# P02_MPU1_JTAG.net
KiCad netlist of a schematic drawn in Altium Designer
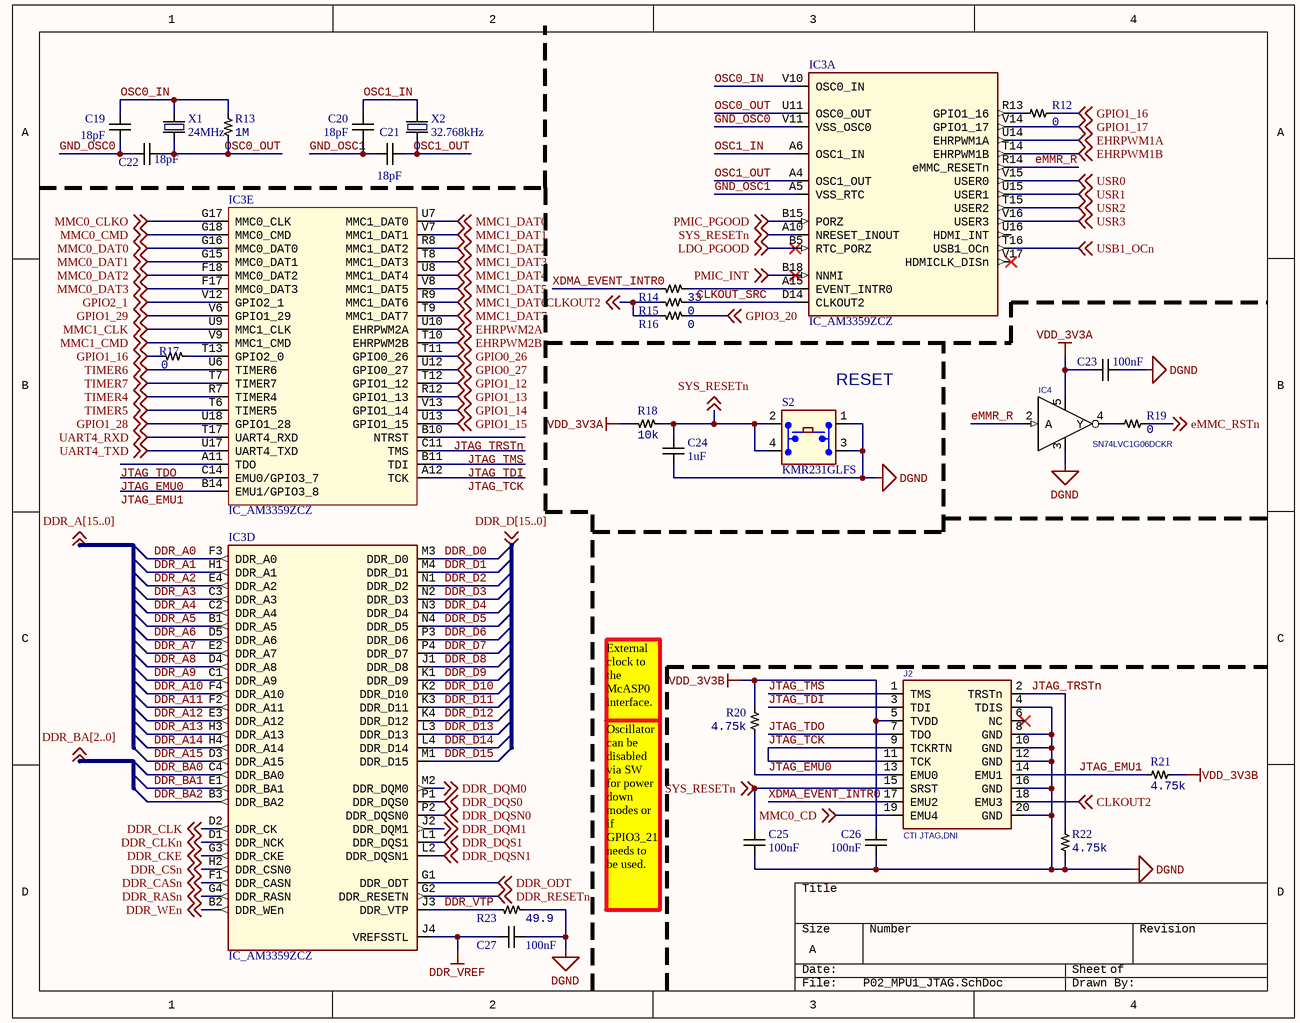
[diagram p0: P02_MPU1_JTAG.SchDoc]

(export (version "E")
  (design (tool "Eeschema 10.0.6"))
  (components
    (comp (ref "C19")
      (value "CC0402JRNPO9BN180")
      (footprint "Orient:CAP0402")
      (description "MLCC 18pF 0402 SMD")
      (fields
        (field (name "MANUFACTURER") "Yageo")
        (field (name "CAPACITANCE") "18pF")
        (field (name "TOLERANCE") "5%")
      )
      (libsource (lib "Orient") (part "CAP_18pF"))
    )
    (comp (ref "C20")
      (value "CC0402JRNPO9BN180")
      (footprint "Orient:CAP0402")
      (description "MLCC 18pF 0402 SMD")
      (fields
        (field (name "MANUFACTURER") "Yageo")
        (field (name "CAPACITANCE") "18pF")
        (field (name "TOLERANCE") "5%")
      )
      (libsource (lib "Orient") (part "CAP_18pF"))
    )
    (comp (ref "C21")
      (value "CC0402JRNPO9BN180")
      (footprint "Orient:CAP0402")
      (description "MLCC 18pF 0402 SMD")
      (fields
        (field (name "MANUFACTURER") "Yageo")
        (field (name "CAPACITANCE") "18pF")
        (field (name "TOLERANCE") "5%")
      )
      (libsource (lib "Orient") (part "CAP_18pF"))
    )
    (comp (ref "C22")
      (value "CC0402JRNPO9BN180")
      (footprint "Orient:CAP0402")
      (description "MLCC 18pF 0402 SMD")
      (fields
        (field (name "MANUFACTURER") "Yageo")
        (field (name "CAPACITANCE") "18pF")
        (field (name "TOLERANCE") "5%")
      )
      (libsource (lib "Orient") (part "CAP_18pF"))
    )
    (comp (ref "C23")
      (value "C0402C104K4RACTU")
      (footprint "Orient:CAP0402")
      (description "MLCC 100nF 0402 SMD")
      (fields
        (field (name "MANUFACTURER") "KEMET")
        (field (name "TOLERANCE") "10%")
        (field (name "CAPACITANCE") "100nF")
      )
      (libsource (lib "Orient") (part "CAP_100nF"))
    )
    (comp (ref "C24")
      (value "CC0402KRX5R6BB105")
      (footprint "Orient:CAP0402")
      (description "MLCC 1uF 0402 SMD")
      (fields
        (field (name "CAPACITANCE") "1uF")
        (field (name "MANUFACTURER") "Yageo")
        (field (name "TOLERANCE") "10%")
      )
      (libsource (lib "Orient") (part "CAP_1uF"))
    )
    (comp (ref "C25")
      (value "C0402C104K4RACTU")
      (footprint "Orient:CAP0402")
      (description "MLCC 100nF 0402 SMD")
      (fields
        (field (name "MANUFACTURER") "KEMET")
        (field (name "TOLERANCE") "10%")
        (field (name "CAPACITANCE") "100nF")
      )
      (libsource (lib "Orient") (part "CAP_100nF"))
    )
    (comp (ref "C26")
      (value "C0402C104K4RACTU")
      (footprint "Orient:CAP0402")
      (description "MLCC 100nF 0402 SMD")
      (fields
        (field (name "MANUFACTURER") "KEMET")
        (field (name "TOLERANCE") "10%")
        (field (name "CAPACITANCE") "100nF")
      )
      (libsource (lib "Orient") (part "CAP_100nF"))
    )
    (comp (ref "C27")
      (value "C0402C104K4RACTU")
      (footprint "Orient:CAP0402")
      (description "MLCC 100nF 0402 SMD")
      (fields
        (field (name "MANUFACTURER") "KEMET")
        (field (name "TOLERANCE") "10%")
        (field (name "CAPACITANCE") "100nF")
      )
      (libsource (lib "Orient") (part "CAP_100nF"))
    )
    (comp (ref "IC3")
      (value "IC_AM3359ZCZ")
      (footprint "Orient:BGA-324")
      (description "SubArctic Cortex A8 Processor 18x18")
      (fields
        (field (name "MANUFACTURER") "Texas Instruments")
        (field (name "MANUFACTURER PART NUMBER") "XAM3359ZCZ")
      )
      (libsource (lib "Orient") (part "IC_AM335X_ZCE_1"))
    )
    (comp (ref "IC4")
      (value "SN74LVC1G06DCKR")
      (footprint "Orient:SC70_DCK")
      (description "IC INVERTER SINGLE 1INPUT SC705")
      (fields
        (field (name "MANUFACTURER") "Texas Instruments")
        (field (name "MANUFACTURER PART NUMBER") "SN74LVC1G06DCKTG4")
      )
      (libsource (lib "Orient") (part "IC_Inverter"))
    )
    (comp (ref "J2")
      (value "CTI JTAG,DNI")
      (description "Dual Line Header 10x2pin Tin")
      (fields
        (field (name "MANUFACTURER") "Samtec Inc")
        (field (name "MANUFACTURER PART NUMBER") "FTR-110-03-G-D-06")
      )
      (libsource (lib "Orient") (part "HDR_10x2_CJTAG"))
    )
    (comp (ref "R12")
      (value "RC0402JR-070RL")
      (footprint "Orient:RES0402")
      (description "Resistor 0Ohm 0402 SMD")
      (fields
        (field (name "MANUFACTURER") "Yageo")
        (field (name "TOLERANCE") "5%")
        (field (name "RESISTANCE") "0")
      )
      (libsource (lib "Orient") (part "RES_0"))
    )
    (comp (ref "R13")
      (value "RC0402FR-071ML")
      (footprint "Orient:RES0402")
      (description "Resistor 1MOhm 0402 SMD")
      (fields
        (field (name "MANUFACTURER") "Yageo")
        (field (name "TOLERANCE") "1%")
        (field (name "RESISTANCE") "1M")
      )
      (libsource (lib "Orient") (part "RES_1M"))
    )
    (comp (ref "R14")
      (value "RC0402FR-0733RL")
      (footprint "Orient:RES0402")
      (description "Resistor 33Ohm 0402 SMD")
      (fields
        (field (name "MANUFACTURER") "Yageo")
        (field (name "TOLERANCE") "1%")
        (field (name "RESISTANCE") "33")
      )
      (libsource (lib "Orient") (part "RES_33"))
    )
    (comp (ref "R15")
      (value "RC0402JR-070RL")
      (footprint "Orient:RES0402")
      (description "Resistor 0Ohm 0402 SMD")
      (fields
        (field (name "MANUFACTURER") "Yageo")
        (field (name "TOLERANCE") "5%")
        (field (name "RESISTANCE") "0")
      )
      (libsource (lib "Orient") (part "RES_0"))
    )
    (comp (ref "R16")
      (value "RC0402JR-070RL")
      (footprint "Orient:RES0402")
      (description "Resistor 0Ohm 0402 SMD")
      (fields
        (field (name "MANUFACTURER") "Yageo")
        (field (name "TOLERANCE") "5%")
        (field (name "RESISTANCE") "0")
      )
      (libsource (lib "Orient") (part "RES_0"))
    )
    (comp (ref "R17")
      (value "RC0402JR-070RL")
      (footprint "Orient:RES0402")
      (description "Resistor 0Ohm 0402 SMD")
      (fields
        (field (name "MANUFACTURER") "Yageo")
        (field (name "TOLERANCE") "5%")
        (field (name "RESISTANCE") "0")
      )
      (libsource (lib "Orient") (part "RES_0"))
    )
    (comp (ref "R18")
      (value "RC0402FR-0710KL")
      (footprint "Orient:RES0402")
      (description "Resistor 10kOhm 0402 SMD")
      (fields
        (field (name "MANUFACTURER") "Yageo")
        (field (name "TOLERANCE") "1%")
        (field (name "RESISTANCE") "10k")
      )
      (libsource (lib "Orient") (part "RES_10k"))
    )
    (comp (ref "R19")
      (value "RC0402JR-070RL")
      (footprint "Orient:RES0402")
      (description "Resistor 0Ohm 0402 SMD")
      (fields
        (field (name "MANUFACTURER") "Yageo")
        (field (name "TOLERANCE") "5%")
        (field (name "RESISTANCE") "0")
      )
      (libsource (lib "Orient") (part "RES_0"))
    )
    (comp (ref "R20")
      (value "RC0402FR-074K75L")
      (footprint "Orient:RES0402")
      (description "Resistor 4.75kOhm 0402 SMD")
      (fields
        (field (name "MANUFACTURER") "Yageo")
        (field (name "TOLERANCE") "1%")
        (field (name "RESISTANCE") "4.75k")
      )
      (libsource (lib "Orient") (part "RES_4.75k"))
    )
    (comp (ref "R21")
      (value "RC0402FR-074K75L")
      (footprint "Orient:RES0402")
      (description "Resistor 4.75kOhm 0402 SMD")
      (fields
        (field (name "MANUFACTURER") "Yageo")
        (field (name "TOLERANCE") "1%")
        (field (name "RESISTANCE") "4.75k")
      )
      (libsource (lib "Orient") (part "RES_4.75k"))
    )
    (comp (ref "R22")
      (value "RC0402FR-074K75L")
      (footprint "Orient:RES0402")
      (description "Resistor 4.75kOhm 0402 SMD")
      (fields
        (field (name "MANUFACTURER") "Yageo")
        (field (name "TOLERANCE") "1%")
        (field (name "RESISTANCE") "4.75k")
      )
      (libsource (lib "Orient") (part "RES_4.75k"))
    )
    (comp (ref "R23")
      (value "RC0402FR-0749R9")
      (footprint "Orient:RES0402")
      (description "Resistor 49.9Ohm 0402 SMD")
      (fields
        (field (name "MANUFACTURER") "Yageo")
        (field (name "MANUFACTURER PART NUMBER") "RC0402FR-0749R9L")
        (field (name "RESISTANCE") "49.9")
      )
      (libsource (lib "Orient") (part "RES_49.9"))
    )
    (comp (ref "S2")
      (value "KMR231GLFS")
      (footprint "Orient:SW4SMD_63X161LS")
      (description "Microminiature Tact Switch for SMT")
      (fields (field (name "MANUFACTURER") "C&K Components"))
      (libsource (lib "Orient") (part "KMR2"))
    )
    (comp (ref "X1")
      (value "24MHz")
      (footprint "Orient:XTAL150SMD_125X196")
      (description "CRYSTAL 24.000MHZ 18PF SMD")
      (fields
        (field (name "MANUFACTURER") "TXC CORPORATION")
        (field (name "MANUFACTURER PART NUMBER") "7A-24.000MAAJ-T")
      )
      (libsource (lib "Orient") (part "CRYS_24MHz_SCC"))
    )
    (comp (ref "X2")
      (value "32.768kHz")
      (footprint "Orient:SOJ-4")
      (description "CRYSTAL 32.768KHZ 12.5PF SMD")
      (fields
        (field (name "MANUFACTURER") "Citizen Finetech Miyota")
        (field (name "MANUFACTURER PART NUMBER") "CM200C-32.768KAZF-UT")
      )
      (libsource (lib "Orient") (part "CRYS_32.768kHz"))
    )
  )
  (nets
    (net (code "1") (name "/CLKOUT_SRC") (class "Default")
      (node (ref "IC3") (pin "D14") (pinfunction "CLKOUT2_D14") (pintype "bidirectional"))
      (node (ref "R15") (pin "1") (pintype "passive"))
    )
    (net (code "2") (name "/DDR_VTP") (class "Default")
      (node (ref "IC3") (pin "J3") (pinfunction "DDR_VTP_J3") (pintype "passive"))
      (node (ref "R23") (pin "2") (pintype "passive"))
    )
    (net (code "3") (name "/GND_OSC0") (class "Default")
      (node (ref "C19") (pin "2") (pintype "passive"))
      (node (ref "C22") (pin "1") (pintype "passive"))
      (node (ref "IC3") (pin "V11") (pinfunction "VSS_OSC0_V11") (pintype "power_in"))
    )
    (net (code "4") (name "/GND_OSC1") (class "Default")
      (node (ref "C20") (pin "1") (pintype "passive"))
      (node (ref "C21") (pin "2") (pintype "passive"))
      (node (ref "IC3") (pin "A5") (pinfunction "VSS_RTC_A5") (pintype "power_in"))
    )
    (net (code "5") (name "/JTAG_EMU0") (class "Default")
      (node (ref "IC3") (pin "C14") (pinfunction "EMU0/GPIO3_7_C14") (pintype "passive"))
      (node (ref "J2") (pin "13") (pinfunction "EMU0_13") (pintype "passive"))
      (node (ref "R20") (pin "1") (pintype "passive"))
    )
    (net (code "6") (name "/JTAG_EMU1") (class "Default")
      (node (ref "IC3") (pin "B14") (pinfunction "EMU1/GPIO3_8_B14") (pintype "passive"))
      (node (ref "J2") (pin "14") (pinfunction "EMU1_14") (pintype "passive"))
      (node (ref "R21") (pin "2") (pintype "passive"))
    )
    (net (code "7") (name "/JTAG_TCK") (class "Default")
      (node (ref "IC3") (pin "A12") (pinfunction "TCK_A12") (pintype "passive"))
      (node (ref "J2") (pin "11") (pinfunction "TCK_11") (pintype "passive"))
      (node (ref "J2") (pin "9") (pinfunction "TCKRTN_9") (pintype "passive"))
    )
    (net (code "8") (name "/JTAG_TDI") (class "Default")
      (node (ref "IC3") (pin "B11") (pinfunction "TDI_B11") (pintype "passive"))
      (node (ref "J2") (pin "3") (pinfunction "TDI_3") (pintype "passive"))
    )
    (net (code "9") (name "/JTAG_TDO") (class "Default")
      (node (ref "IC3") (pin "A11") (pinfunction "TDO_A11") (pintype "passive"))
      (node (ref "J2") (pin "7") (pinfunction "TDO_7") (pintype "passive"))
    )
    (net (code "10") (name "/JTAG_TMS") (class "Default")
      (node (ref "IC3") (pin "C11") (pinfunction "TMS_C11") (pintype "passive"))
      (node (ref "J2") (pin "1") (pinfunction "TMS_1") (pintype "passive"))
    )
    (net (code "11") (name "/JTAG_TRSTn") (class "Default")
      (node (ref "IC3") (pin "B10") (pinfunction "NTRST_B10") (pintype "passive"))
      (node (ref "J2") (pin "2") (pinfunction "TRSTn_2") (pintype "passive"))
      (node (ref "R22") (pin "2") (pintype "passive"))
    )
    (net (code "12") (name "/OSC0_IN") (class "Default")
      (node (ref "C19") (pin "1") (pintype "passive"))
      (node (ref "IC3") (pin "V10") (pinfunction "OSC0_IN_V10") (pintype "passive"))
      (node (ref "R13") (pin "2") (pintype "passive"))
      (node (ref "X1") (pin "2") (pinfunction "2_2") (pintype "passive"))
    )
    (net (code "13") (name "/OSC0_OUT") (class "Default")
      (node (ref "C22") (pin "2") (pintype "passive"))
      (node (ref "IC3") (pin "U11") (pinfunction "OSC0_OUT_U11") (pintype "passive"))
      (node (ref "R13") (pin "1") (pintype "passive"))
      (node (ref "X1") (pin "1") (pinfunction "1_1") (pintype "passive"))
    )
    (net (code "14") (name "/OSC1_IN") (class "Default")
      (node (ref "C20") (pin "2") (pintype "passive"))
      (node (ref "IC3") (pin "A6") (pinfunction "OSC1_IN_A6") (pintype "passive"))
      (node (ref "X2") (pin "1") (pinfunction "1_1") (pintype "passive"))
    )
    (net (code "15") (name "/OSC1_OUT") (class "Default")
      (node (ref "C21") (pin "1") (pintype "passive"))
      (node (ref "IC3") (pin "A4") (pinfunction "OSC1_OUT_A4") (pintype "passive"))
      (node (ref "X2") (pin "4") (pinfunction "4_4") (pintype "passive"))
    )
    (net (code "16") (name "/XDMA_EVENT_INTR0") (class "Default")
      (node (ref "J2") (pin "17") (pinfunction "EMU2_17") (pintype "passive"))
      (node (ref "R14") (pin "1") (pintype "passive"))
    )
    (net (code "17") (name "/eMMR_R") (class "Default")
      (node (ref "IC3") (pin "R14") (pinfunction "eMMC_RESETn_R14") (pintype "output"))
      (node (ref "IC4") (pin "2") (pinfunction "A_2") (pintype "input"))
    )
    (net (code "18") (name "CLKOUT2") (class "Default")
      (node (ref "J2") (pin "18") (pinfunction "EMU3_18") (pintype "passive"))
      (node (ref "R15") (pin "2") (pintype "passive"))
      (node (ref "R16") (pin "2") (pintype "passive"))
    )
    (net (code "19") (name "DDR_A0") (class "Default")
      (node (ref "IC3") (pin "F3") (pinfunction "DDR_A0_F3") (pintype "output"))
    )
    (net (code "20") (name "DDR_A1") (class "Default")
      (node (ref "IC3") (pin "H1") (pinfunction "DDR_A1_H1") (pintype "output"))
    )
    (net (code "21") (name "DDR_A2") (class "Default")
      (node (ref "IC3") (pin "E4") (pinfunction "DDR_A2_E4") (pintype "output"))
    )
    (net (code "22") (name "DDR_A3") (class "Default")
      (node (ref "IC3") (pin "C3") (pinfunction "DDR_A3_C3") (pintype "output"))
    )
    (net (code "23") (name "DDR_A4") (class "Default")
      (node (ref "IC3") (pin "C2") (pinfunction "DDR_A4_C2") (pintype "output"))
    )
    (net (code "24") (name "DDR_A5") (class "Default")
      (node (ref "IC3") (pin "B1") (pinfunction "DDR_A5_B1") (pintype "output"))
    )
    (net (code "25") (name "DDR_A6") (class "Default")
      (node (ref "IC3") (pin "D5") (pinfunction "DDR_A6_D5") (pintype "output"))
    )
    (net (code "26") (name "DDR_A7") (class "Default")
      (node (ref "IC3") (pin "E2") (pinfunction "DDR_A7_E2") (pintype "output"))
    )
    (net (code "27") (name "DDR_A8") (class "Default")
      (node (ref "IC3") (pin "D4") (pinfunction "DDR_A8_D4") (pintype "output"))
    )
    (net (code "28") (name "DDR_A9") (class "Default")
      (node (ref "IC3") (pin "C1") (pinfunction "DDR_A9_C1") (pintype "output"))
    )
    (net (code "29") (name "DDR_A10") (class "Default")
      (node (ref "IC3") (pin "F4") (pinfunction "DDR_A10_F4") (pintype "output"))
    )
    (net (code "30") (name "DDR_A11") (class "Default")
      (node (ref "IC3") (pin "F2") (pinfunction "DDR_A11_F2") (pintype "output"))
    )
    (net (code "31") (name "DDR_A12") (class "Default")
      (node (ref "IC3") (pin "E3") (pinfunction "DDR_A12_E3") (pintype "output"))
    )
    (net (code "32") (name "DDR_A13") (class "Default")
      (node (ref "IC3") (pin "H3") (pinfunction "DDR_A13_H3") (pintype "output"))
    )
    (net (code "33") (name "DDR_A14") (class "Default")
      (node (ref "IC3") (pin "H4") (pinfunction "DDR_A14_H4") (pintype "output"))
    )
    (net (code "34") (name "DDR_A15") (class "Default")
      (node (ref "IC3") (pin "D3") (pinfunction "DDR_A15_D3") (pintype "output"))
    )
    (net (code "36") (name "DDR_BA0") (class "Default")
      (node (ref "IC3") (pin "C4") (pinfunction "DDR_BA0_C4") (pintype "output"))
    )
    (net (code "37") (name "DDR_BA1") (class "Default")
      (node (ref "IC3") (pin "E1") (pinfunction "DDR_BA1_E1") (pintype "output"))
    )
    (net (code "38") (name "DDR_BA2") (class "Default")
      (node (ref "IC3") (pin "B3") (pinfunction "DDR_BA2_B3") (pintype "output"))
    )
    (net (code "40") (name "DDR_CASn") (class "Default")
      (node (ref "IC3") (pin "F1") (pinfunction "DDR_CASN_F1") (pintype "output"))
    )
    (net (code "41") (name "DDR_CKE") (class "Default")
      (node (ref "IC3") (pin "G3") (pinfunction "DDR_CKE_G3") (pintype "output"))
    )
    (net (code "42") (name "DDR_CLK") (class "Default")
      (node (ref "IC3") (pin "D2") (pinfunction "DDR_CK_D2") (pintype "output"))
    )
    (net (code "43") (name "DDR_CLKn") (class "Default")
      (node (ref "IC3") (pin "D1") (pinfunction "DDR_NCK_D1") (pintype "output"))
    )
    (net (code "44") (name "DDR_CSn") (class "Default")
      (node (ref "IC3") (pin "H2") (pinfunction "DDR_CSN0_H2") (pintype "output"))
    )
    (net (code "45") (name "DDR_D0") (class "Default")
      (node (ref "IC3") (pin "M3") (pinfunction "DDR_D0_M3") (pintype "bidirectional"))
    )
    (net (code "46") (name "DDR_D1") (class "Default")
      (node (ref "IC3") (pin "M4") (pinfunction "DDR_D1_M4") (pintype "bidirectional"))
    )
    (net (code "47") (name "DDR_D2") (class "Default")
      (node (ref "IC3") (pin "N1") (pinfunction "DDR_D2_N1") (pintype "bidirectional"))
    )
    (net (code "48") (name "DDR_D3") (class "Default")
      (node (ref "IC3") (pin "N2") (pinfunction "DDR_D3_N2") (pintype "bidirectional"))
    )
    (net (code "49") (name "DDR_D4") (class "Default")
      (node (ref "IC3") (pin "N3") (pinfunction "DDR_D4_N3") (pintype "bidirectional"))
    )
    (net (code "50") (name "DDR_D5") (class "Default")
      (node (ref "IC3") (pin "N4") (pinfunction "DDR_D5_N4") (pintype "bidirectional"))
    )
    (net (code "51") (name "DDR_D6") (class "Default")
      (node (ref "IC3") (pin "P3") (pinfunction "DDR_D6_P3") (pintype "bidirectional"))
    )
    (net (code "52") (name "DDR_D7") (class "Default")
      (node (ref "IC3") (pin "P4") (pinfunction "DDR_D7_P4") (pintype "bidirectional"))
    )
    (net (code "53") (name "DDR_D8") (class "Default")
      (node (ref "IC3") (pin "J1") (pinfunction "DDR_D8_J1") (pintype "bidirectional"))
    )
    (net (code "54") (name "DDR_D9") (class "Default")
      (node (ref "IC3") (pin "K1") (pinfunction "DDR_D9_K1") (pintype "bidirectional"))
    )
    (net (code "55") (name "DDR_D10") (class "Default")
      (node (ref "IC3") (pin "K2") (pinfunction "DDR_D10_K2") (pintype "bidirectional"))
    )
    (net (code "56") (name "DDR_D11") (class "Default")
      (node (ref "IC3") (pin "K3") (pinfunction "DDR_D11_K3") (pintype "bidirectional"))
    )
    (net (code "57") (name "DDR_D12") (class "Default")
      (node (ref "IC3") (pin "K4") (pinfunction "DDR_D12_K4") (pintype "bidirectional"))
    )
    (net (code "58") (name "DDR_D13") (class "Default")
      (node (ref "IC3") (pin "L3") (pinfunction "DDR_D13_L3") (pintype "bidirectional"))
    )
    (net (code "59") (name "DDR_D14") (class "Default")
      (node (ref "IC3") (pin "L4") (pinfunction "DDR_D14_L4") (pintype "bidirectional"))
    )
    (net (code "60") (name "DDR_D15") (class "Default")
      (node (ref "IC3") (pin "M1") (pinfunction "DDR_D15_M1") (pintype "bidirectional"))
    )
    (net (code "61") (name "DDR_DQM0") (class "Default")
      (node (ref "IC3") (pin "M2") (pinfunction "DDR_DQM0_M2") (pintype "output"))
    )
    (net (code "62") (name "DDR_DQM1") (class "Default")
      (node (ref "IC3") (pin "J2") (pinfunction "DDR_DQM1_J2") (pintype "output"))
    )
    (net (code "63") (name "DDR_DQS0") (class "Default")
      (node (ref "IC3") (pin "P1") (pinfunction "DDR_DQS0_P1") (pintype "bidirectional"))
    )
    (net (code "64") (name "DDR_DQS1") (class "Default")
      (node (ref "IC3") (pin "L1") (pinfunction "DDR_DQS1_L1") (pintype "bidirectional"))
    )
    (net (code "65") (name "DDR_DQSN0") (class "Default")
      (node (ref "IC3") (pin "P2") (pinfunction "DDR_DQSN0_P2") (pintype "bidirectional"))
    )
    (net (code "66") (name "DDR_DQSN1") (class "Default")
      (node (ref "IC3") (pin "L2") (pinfunction "DDR_DQSN1_L2") (pintype "bidirectional"))
    )
    (net (code "68") (name "DDR_ODT") (class "Default")
      (node (ref "IC3") (pin "G1") (pinfunction "DDR_ODT_G1") (pintype "passive"))
    )
    (net (code "69") (name "DDR_RASn") (class "Default")
      (node (ref "IC3") (pin "G4") (pinfunction "DDR_RASN_G4") (pintype "output"))
    )
    (net (code "70") (name "DDR_RESETn") (class "Default")
      (node (ref "IC3") (pin "G2") (pinfunction "DDR_RESETN_G2") (pintype "output"))
    )
    (net (code "71") (name "DDR_VREF") (class "Default")
      (node (ref "C27") (pin "1") (pintype "passive"))
      (node (ref "IC3") (pin "J4") (pinfunction "VREFSSTL_J4") (pintype "passive"))
    )
    (net (code "72") (name "DDR_WEn") (class "Default")
      (node (ref "IC3") (pin "B2") (pinfunction "DDR_WEn_B2") (pintype "output"))
    )
    (net (code "73") (name "DGND") (class "Default")
      (node (ref "C23") (pin "1") (pintype "passive"))
      (node (ref "C24") (pin "1") (pintype "passive"))
      (node (ref "C25") (pin "2") (pintype "passive"))
      (node (ref "C26") (pin "2") (pintype "passive"))
      (node (ref "C27") (pin "2") (pintype "passive"))
      (node (ref "IC4") (pin "3") (pinfunction "GND_3") (pintype "power_in"))
      (node (ref "J2") (pin "10") (pinfunction "GND_10") (pintype "power_in"))
      (node (ref "J2") (pin "12") (pinfunction "GND_12") (pintype "power_in"))
      (node (ref "J2") (pin "16") (pinfunction "GND_16") (pintype "power_in"))
      (node (ref "J2") (pin "20") (pinfunction "GND_20") (pintype "power_in"))
      (node (ref "J2") (pin "4") (pinfunction "TDIS_4") (pintype "passive"))
      (node (ref "J2") (pin "8") (pinfunction "GND_8") (pintype "power_in"))
      (node (ref "R22") (pin "1") (pintype "passive"))
      (node (ref "R23") (pin "1") (pintype "passive"))
      (node (ref "S2") (pin "1") (pinfunction "A1_1") (pintype "passive"))
      (node (ref "S2") (pin "3") (pinfunction "A3_3") (pintype "passive"))
    )
    (net (code "74") (name "EHRPWM1A") (class "Default")
      (node (ref "IC3") (pin "U14") (pinfunction "EHRPWM1A_U14") (pintype "output"))
    )
    (net (code "75") (name "EHRPWM1B") (class "Default")
      (node (ref "IC3") (pin "T14") (pinfunction "EHRPWM1B_T14") (pintype "output"))
    )
    (net (code "76") (name "EHRPWM2A") (class "Default")
      (node (ref "IC3") (pin "U10") (pinfunction "EHRPWM2A_U10") (pintype "bidirectional"))
    )
    (net (code "77") (name "EHRPWM2B") (class "Default")
      (node (ref "IC3") (pin "T10") (pinfunction "EHRPWM2B_T10") (pintype "bidirectional"))
    )
    (net (code "78") (name "GPIO0_26") (class "Default")
      (node (ref "IC3") (pin "T11") (pinfunction "GPIO0_26_T11") (pintype "bidirectional"))
    )
    (net (code "79") (name "GPIO0_27") (class "Default")
      (node (ref "IC3") (pin "U12") (pinfunction "GPIO0_27_U12") (pintype "bidirectional"))
    )
    (net (code "80") (name "GPIO1_12") (class "Default")
      (node (ref "IC3") (pin "T12") (pinfunction "GPIO1_12_T12") (pintype "bidirectional"))
    )
    (net (code "81") (name "GPIO1_13") (class "Default")
      (node (ref "IC3") (pin "R12") (pinfunction "GPIO1_13_R12") (pintype "bidirectional"))
    )
    (net (code "82") (name "GPIO1_14") (class "Default")
      (node (ref "IC3") (pin "V13") (pinfunction "GPIO1_14_V13") (pintype "bidirectional"))
    )
    (net (code "83") (name "GPIO1_15") (class "Default")
      (node (ref "IC3") (pin "U13") (pinfunction "GPIO1_15_U13") (pintype "bidirectional"))
    )
    (net (code "84") (name "GPIO1_16") (class "Default")
      (node (ref "R12") (pin "2") (pintype "passive"))
      (node (ref "R17") (pin "2") (pintype "passive"))
    )
    (net (code "85") (name "GPIO1_17") (class "Default")
      (node (ref "IC3") (pin "V14") (pinfunction "GPIO1_17_V14") (pintype "output"))
    )
    (net (code "86") (name "GPIO1_28") (class "Default")
      (node (ref "IC3") (pin "U18") (pinfunction "GPIO1_28_U18") (pintype "bidirectional"))
    )
    (net (code "87") (name "GPIO1_29") (class "Default")
      (node (ref "IC3") (pin "V6") (pinfunction "GPIO1_29_V6") (pintype "bidirectional"))
    )
    (net (code "88") (name "GPIO2_1") (class "Default")
      (node (ref "IC3") (pin "V12") (pinfunction "GPIO2_1_V12") (pintype "bidirectional"))
    )
    (net (code "89") (name "GPIO3_20") (class "Default") (node (ref "R16") (pin "1") (pintype "passive")))
    (net (code "90") (name "LDO_PGOOD") (class "Default")
      (node (ref "IC3") (pin "B5") (pinfunction "RTC_PORZ_B5") (pintype "input"))
    )
    (net (code "91") (name "MMC0_CD") (class "Default")
      (node (ref "J2") (pin "19") (pinfunction "EMU4_19") (pintype "passive"))
    )
    (net (code "92") (name "MMC0_CLKO") (class "Default")
      (node (ref "IC3") (pin "G17") (pinfunction "MMC0_CLK_G17") (pintype "bidirectional"))
    )
    (net (code "93") (name "MMC0_CMD") (class "Default")
      (node (ref "IC3") (pin "G18") (pinfunction "MMC0_CMD_G18") (pintype "bidirectional"))
    )
    (net (code "94") (name "MMC0_DAT0") (class "Default")
      (node (ref "IC3") (pin "G16") (pinfunction "MMC0_DAT0_G16") (pintype "bidirectional"))
    )
    (net (code "95") (name "MMC0_DAT1") (class "Default")
      (node (ref "IC3") (pin "G15") (pinfunction "MMC0_DAT1_G15") (pintype "bidirectional"))
    )
    (net (code "96") (name "MMC0_DAT2") (class "Default")
      (node (ref "IC3") (pin "F18") (pinfunction "MMC0_DAT2_F18") (pintype "bidirectional"))
    )
    (net (code "97") (name "MMC0_DAT3") (class "Default")
      (node (ref "IC3") (pin "F17") (pinfunction "MMC0_DAT3_F17") (pintype "bidirectional"))
    )
    (net (code "98") (name "MMC1_CLK") (class "Default")
      (node (ref "IC3") (pin "U9") (pinfunction "MMC1_CLK_U9") (pintype "bidirectional"))
    )
    (net (code "99") (name "MMC1_CMD") (class "Default")
      (node (ref "IC3") (pin "V9") (pinfunction "MMC1_CMD_V9") (pintype "bidirectional"))
    )
    (net (code "100") (name "MMC1_DAT0") (class "Default")
      (node (ref "IC3") (pin "U7") (pinfunction "MMC1_DAT0_U7") (pintype "bidirectional"))
    )
    (net (code "101") (name "MMC1_DAT1") (class "Default")
      (node (ref "IC3") (pin "V7") (pinfunction "MMC1_DAT1_V7") (pintype "bidirectional"))
    )
    (net (code "102") (name "MMC1_DAT2") (class "Default")
      (node (ref "IC3") (pin "R8") (pinfunction "MMC1_DAT2_R8") (pintype "bidirectional"))
    )
    (net (code "103") (name "MMC1_DAT3") (class "Default")
      (node (ref "IC3") (pin "T8") (pinfunction "MMC1_DAT3_T8") (pintype "bidirectional"))
    )
    (net (code "104") (name "MMC1_DAT4") (class "Default")
      (node (ref "IC3") (pin "U8") (pinfunction "MMC1_DAT4_U8") (pintype "bidirectional"))
    )
    (net (code "105") (name "MMC1_DAT5") (class "Default")
      (node (ref "IC3") (pin "V8") (pinfunction "MMC1_DAT5_V8") (pintype "bidirectional"))
    )
    (net (code "106") (name "MMC1_DAT6") (class "Default")
      (node (ref "IC3") (pin "R9") (pinfunction "MMC1_DAT6_R9") (pintype "bidirectional"))
    )
    (net (code "107") (name "MMC1_DAT7") (class "Default")
      (node (ref "IC3") (pin "T9") (pinfunction "MMC1_DAT7_T9") (pintype "bidirectional"))
    )
    (net (code "108") (name "Net-(IC3A-EVENT_INTR0)") (class "Default")
      (node (ref "IC3") (pin "A15") (pinfunction "EVENT_INTR0_A15") (pintype "bidirectional"))
      (node (ref "R14") (pin "2") (pintype "passive"))
    )
    (net (code "109") (name "Net-(IC3A-GPIO1_16)") (class "Default")
      (node (ref "IC3") (pin "R13") (pinfunction "GPIO1_16_R13") (pintype "output"))
      (node (ref "R12") (pin "1") (pintype "passive"))
    )
    (net (code "110") (name "Net-(IC3E-GPIO2_0)") (class "Default")
      (node (ref "IC3") (pin "T13") (pinfunction "GPIO2_0_T13") (pintype "bidirectional"))
      (node (ref "R17") (pin "1") (pintype "passive"))
    )
    (net (code "111") (name "Net-(IC4-Y)") (class "Default")
      (node (ref "IC4") (pin "4") (pinfunction "Y_4") (pintype "open_collector"))
      (node (ref "R19") (pin "1") (pintype "passive"))
    )
    (net (code "112") (name "PMIC_INT") (class "Default")
      (node (ref "IC3") (pin "B18") (pinfunction "NNMI_B18") (pintype "input"))
    )
    (net (code "113") (name "PMIC_PGOOD") (class "Default")
      (node (ref "IC3") (pin "B15") (pinfunction "PORZ_B15") (pintype "input"))
    )
    (net (code "114") (name "SYS_RESETn") (class "Default")
      (node (ref "C24") (pin "2") (pintype "passive"))
      (node (ref "C25") (pin "1") (pintype "passive"))
      (node (ref "IC3") (pin "A10") (pinfunction "NRESET_INOUT_A10") (pintype "bidirectional"))
      (node (ref "J2") (pin "15") (pinfunction "SRST_15") (pintype "passive"))
      (node (ref "R18") (pin "2") (pintype "passive"))
      (node (ref "S2") (pin "2") (pinfunction "A2_2") (pintype "passive"))
      (node (ref "S2") (pin "4") (pinfunction "4_4") (pintype "power_in"))
    )
    (net (code "115") (name "TIMER4") (class "Default")
      (node (ref "IC3") (pin "R7") (pinfunction "TIMER4_R7") (pintype "bidirectional"))
    )
    (net (code "116") (name "TIMER5") (class "Default")
      (node (ref "IC3") (pin "T6") (pinfunction "TIMER5_T6") (pintype "bidirectional"))
    )
    (net (code "117") (name "TIMER6") (class "Default")
      (node (ref "IC3") (pin "U6") (pinfunction "TIMER6_U6") (pintype "bidirectional"))
    )
    (net (code "118") (name "TIMER7") (class "Default")
      (node (ref "IC3") (pin "T7") (pinfunction "TIMER7_T7") (pintype "bidirectional"))
    )
    (net (code "119") (name "UART4_RXD") (class "Default")
      (node (ref "IC3") (pin "T17") (pinfunction "UART4_RXD_T17") (pintype "bidirectional"))
    )
    (net (code "120") (name "UART4_TXD") (class "Default")
      (node (ref "IC3") (pin "U17") (pinfunction "UART4_TXD_U17") (pintype "bidirectional"))
    )
    (net (code "121") (name "USB1_OCn") (class "Default")
      (node (ref "IC3") (pin "T16") (pinfunction "USB1_OCn_T16") (pintype "output"))
    )
    (net (code "122") (name "USR0") (class "Default")
      (node (ref "IC3") (pin "V15") (pinfunction "USER0_V15") (pintype "output"))
    )
    (net (code "123") (name "USR1") (class "Default")
      (node (ref "IC3") (pin "U15") (pinfunction "USER1_U15") (pintype "output"))
    )
    (net (code "124") (name "USR2") (class "Default")
      (node (ref "IC3") (pin "T15") (pinfunction "USER2_T15") (pintype "output"))
    )
    (net (code "125") (name "USR3") (class "Default")
      (node (ref "IC3") (pin "V16") (pinfunction "USER3_V16") (pintype "output"))
    )
    (net (code "126") (name "VDD_3V3A") (class "Default")
      (node (ref "C23") (pin "2") (pintype "passive"))
      (node (ref "IC4") (pin "5") (pinfunction "VCC_5") (pintype "power_in"))
      (node (ref "R18") (pin "1") (pintype "passive"))
    )
    (net (code "127") (name "VDD_3V3B") (class "Default")
      (node (ref "C26") (pin "1") (pintype "passive"))
      (node (ref "J2") (pin "5") (pinfunction "TVDD_5") (pintype "passive"))
      (node (ref "R20") (pin "2") (pintype "passive"))
      (node (ref "R21") (pin "1") (pintype "passive"))
    )
    (net (code "128") (name "eMMC_RSTn") (class "Default") (node (ref "R19") (pin "2") (pintype "passive")))
    (net (code "129") (name "unconnected-(IC3A-HDMICLK_DISn-PadV17)") (class "Default")
      (node (ref "IC3") (pin "V17") (pinfunction "HDMICLK_DISn_V17") (pintype "output+no_connect"))
    )
    (net (code "130") (name "unconnected-(IC3A-HDMI_INT-PadU16)") (class "Default")
      (node (ref "IC3") (pin "U16") (pinfunction "HDMI_INT_U16") (pintype "output"))
    )
    (net (code "131") (name "unconnected-(J2-NC-Pad6)") (class "Default")
      (node (ref "J2") (pin "6") (pinfunction "NC_6") (pintype "passive+no_connect"))
    )
  )
)
